# 243-436_Interface-Capteurs.net
KiCad netlist of a schematic drawn in Altium Designer
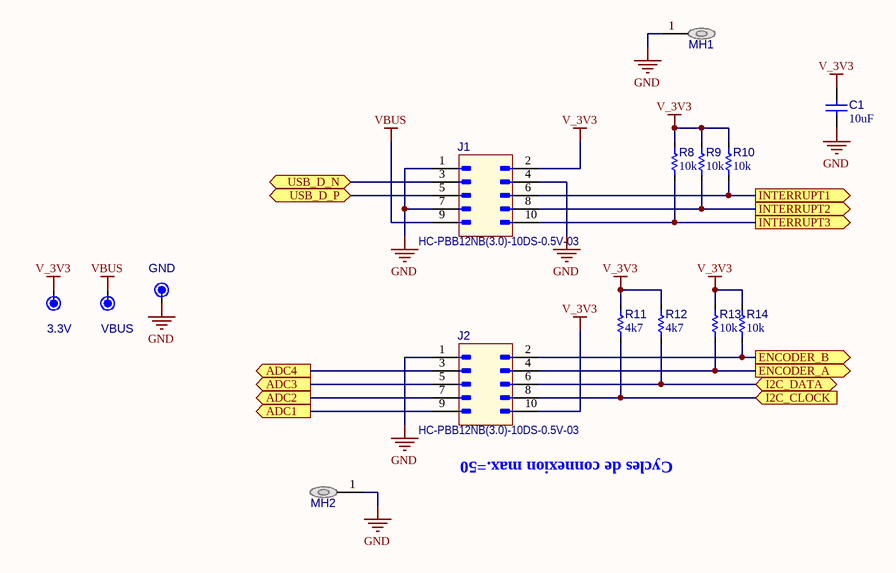
[diagram p0: 243-436_Interface-Capteurs.SchDoc]

(export (version "E")
  (design (tool "Eeschema 10.0.6"))
  (components
    (comp (ref "3.3V")
      (value "DNP")
      (footprint "TP_TH061")
      (description "Pad TH 0.61mm diameter (AWG28)")
      (libsource (lib "243-436_MP_Console") (part "TP_TH0.61mm(AWG28)"))
    )
    (comp (ref "C1")
      (value "10uF")
      (footprint "C_2012[0805]")
      (description "Capacitor type 1")
      (fields (field (name "TOLERANCE") "10%") (field (name "Comment") "CAP CER 10uF 25V X5R 0805"))
      (libsource (lib "TEP_243-Altium_DBLib") (part "capacitor"))
    )
    (comp (ref "GND")
      (value "DNP")
      (footprint "TP_TH061")
      (description "Pad TH 0.61mm diameter (AWG28)")
      (libsource (lib "243-436_MP_Console") (part "TP_TH0.61mm(AWG28)"))
    )
    (comp (ref "J1")
      (value "HC-PBB12NB(3.0)-10DS-0.5V-03")
      (footprint "J_CONN_HDR_2ROW_10POS_0MM5")
      (description "Connector Receptacle 2x5pos, 0,5mm")
      (libsource (lib "243-336_MP_Manette") (part "J_Conn_02x05"))
    )
    (comp (ref "J2")
      (value "HC-PBB12NB(3.0)-10DS-0.5V-03")
      (footprint "J_CONN_HDR_2ROW_10POS_0MM5")
      (description "Connector Receptacle 2x5pos, 0,5mm")
      (libsource (lib "243-336_MP_Manette") (part "J_Conn_02x05"))
    )
    (comp (ref "MH1")
      (value "MP_1.6MM")
      (footprint "MP_M-Hole_M1.6")
      (description "Mounting Hole 1.6mm")
      (libsource (lib "") (part "MP_1.6MM_1"))
    )
    (comp (ref "MH2")
      (value "MP_1.6MM")
      (footprint "MP_M-Hole_M1.6")
      (description "Mounting Hole 1.6mm")
      (libsource (lib "243-336_MP_Manette") (part "MP_1.6MM"))
    )
    (comp (ref "R8")
      (value "10k")
      (footprint "R_1005[0402]")
      (description "Resistor type 1")
      (fields (field (name "TOLERANCE") "1%") (field (name "Comment") "Res 10k 1% 0402"))
      (libsource (lib "TEP_243-Altium_DBLib") (part "resistor"))
    )
    (comp (ref "R9")
      (value "10k")
      (footprint "R_1005[0402]")
      (description "Resistor type 1")
      (fields (field (name "TOLERANCE") "1%") (field (name "Comment") "Res 10k 1% 0402"))
      (libsource (lib "TEP_243-Altium_DBLib") (part "resistor"))
    )
    (comp (ref "R10")
      (value "10k")
      (footprint "R_1005[0402]")
      (description "Resistor type 1")
      (fields (field (name "TOLERANCE") "1%") (field (name "Comment") "Res 10k 1% 0402"))
      (libsource (lib "TEP_243-Altium_DBLib") (part "resistor"))
    )
    (comp (ref "R11")
      (value "4k7")
      (footprint "R_1005[0402]")
      (description "Resistor type 1")
      (fields (field (name "TOLERANCE") "1%") (field (name "Comment") "Res 4k7 1% 0402"))
      (libsource (lib "TEP_243-Altium_DBLib") (part "resistor"))
    )
    (comp (ref "R12")
      (value "4k7")
      (footprint "R_1005[0402]")
      (description "Resistor type 1")
      (fields (field (name "TOLERANCE") "1%") (field (name "Comment") "Res 4k7 1% 0402"))
      (libsource (lib "TEP_243-Altium_DBLib") (part "resistor"))
    )
    (comp (ref "R13")
      (value "10k")
      (footprint "R_1005[0402]")
      (description "Resistor type 1")
      (fields (field (name "TOLERANCE") "1%") (field (name "Comment") "Res 10k 1% 0402"))
      (libsource (lib "TEP_243-Altium_DBLib") (part "resistor"))
    )
    (comp (ref "R14")
      (value "10k")
      (footprint "R_1005[0402]")
      (description "Resistor type 1")
      (fields (field (name "TOLERANCE") "1%") (field (name "Comment") "Res 10k 1% 0402"))
      (libsource (lib "TEP_243-Altium_DBLib") (part "resistor"))
    )
    (comp (ref "VBUS")
      (value "DNP")
      (footprint "TP_TH061")
      (description "Pad TH 0.61mm diameter (AWG28)")
      (libsource (lib "243-436_MP_Console") (part "TP_TH0.61mm(AWG28)"))
    )
  )
  (nets
    (net (code "1") (name "/ADC1") (class "Default")
      (node (ref "J2") (pin "9") (pinfunction "9_9") (pintype "passive"))
    )
    (net (code "2") (name "/ADC2") (class "Default")
      (node (ref "J2") (pin "7") (pinfunction "7_7") (pintype "passive"))
    )
    (net (code "3") (name "/ADC3") (class "Default")
      (node (ref "J2") (pin "5") (pinfunction "5_5") (pintype "passive"))
    )
    (net (code "4") (name "/ADC4") (class "Default")
      (node (ref "J2") (pin "3") (pinfunction "3_3") (pintype "passive"))
    )
    (net (code "5") (name "/ENCODER_A") (class "Default")
      (node (ref "J2") (pin "4") (pinfunction "4_4") (pintype "passive"))
      (node (ref "R13") (pin "1") (pinfunction "1_1") (pintype "passive"))
    )
    (net (code "6") (name "/ENCODER_B") (class "Default")
      (node (ref "J2") (pin "2") (pinfunction "2_2") (pintype "passive"))
      (node (ref "R14") (pin "1") (pinfunction "1_1") (pintype "passive"))
    )
    (net (code "7") (name "/I2C_CLOCK") (class "Default")
      (node (ref "J2") (pin "8") (pinfunction "8_8") (pintype "passive"))
      (node (ref "R11") (pin "1") (pinfunction "1_1") (pintype "passive"))
    )
    (net (code "8") (name "/I2C_DATA") (class "Default")
      (node (ref "J2") (pin "6") (pinfunction "6_6") (pintype "passive"))
      (node (ref "R12") (pin "1") (pinfunction "1_1") (pintype "passive"))
    )
    (net (code "9") (name "/INTERRUPT1") (class "Default")
      (node (ref "J1") (pin "6") (pinfunction "6_6") (pintype "passive"))
      (node (ref "R10") (pin "1") (pinfunction "1_1") (pintype "passive"))
    )
    (net (code "10") (name "/INTERRUPT2") (class "Default")
      (node (ref "J1") (pin "8") (pinfunction "8_8") (pintype "passive"))
      (node (ref "R9") (pin "1") (pinfunction "1_1") (pintype "passive"))
    )
    (net (code "11") (name "/INTERRUPT3") (class "Default")
      (node (ref "J1") (pin "10") (pinfunction "10_10") (pintype "passive"))
      (node (ref "R8") (pin "1") (pinfunction "1_1") (pintype "passive"))
    )
    (net (code "12") (name "/USB_D_N") (class "Default")
      (node (ref "J1") (pin "3") (pinfunction "3_3") (pintype "passive"))
    )
    (net (code "13") (name "/USB_D_P") (class "Default")
      (node (ref "J1") (pin "5") (pinfunction "5_5") (pintype "passive"))
    )
    (net (code "14") (name "GND") (class "Default")
      (node (ref "C1") (pin "1") (pinfunction "1_1") (pintype "passive"))
      (node (ref "GND") (pin "1") (pinfunction "1_1") (pintype "passive"))
      (node (ref "J1") (pin "1") (pinfunction "1_1") (pintype "passive"))
      (node (ref "J1") (pin "4") (pinfunction "4_4") (pintype "passive"))
      (node (ref "J1") (pin "7") (pinfunction "7_7") (pintype "passive"))
      (node (ref "J2") (pin "1") (pinfunction "1_1") (pintype "passive"))
      (node (ref "MH1") (pin "1") (pinfunction "1_1") (pintype "power_in"))
      (node (ref "MH2") (pin "1") (pinfunction "1_1") (pintype "power_in"))
    )
    (net (code "15") (name "VBUS") (class "Default")
      (node (ref "J1") (pin "9") (pinfunction "9_9") (pintype "passive"))
      (node (ref "VBUS") (pin "1") (pinfunction "1_1") (pintype "passive"))
    )
    (net (code "16") (name "V_3V3") (class "Default")
      (node (ref "3.3V") (pin "1") (pinfunction "1_1") (pintype "passive"))
      (node (ref "C1") (pin "2") (pinfunction "2_2") (pintype "passive"))
      (node (ref "J1") (pin "2") (pinfunction "2_2") (pintype "passive"))
      (node (ref "J2") (pin "10") (pinfunction "10_10") (pintype "passive"))
      (node (ref "R10") (pin "2") (pinfunction "2_2") (pintype "passive"))
      (node (ref "R11") (pin "2") (pinfunction "2_2") (pintype "passive"))
      (node (ref "R12") (pin "2") (pinfunction "2_2") (pintype "passive"))
      (node (ref "R13") (pin "2") (pinfunction "2_2") (pintype "passive"))
      (node (ref "R14") (pin "2") (pinfunction "2_2") (pintype "passive"))
      (node (ref "R8") (pin "2") (pinfunction "2_2") (pintype "passive"))
      (node (ref "R9") (pin "2") (pinfunction "2_2") (pintype "passive"))
    )
  )
)
